# Sheet_esp32.net
KiCad netlist of a schematic drawn in Altium Designer
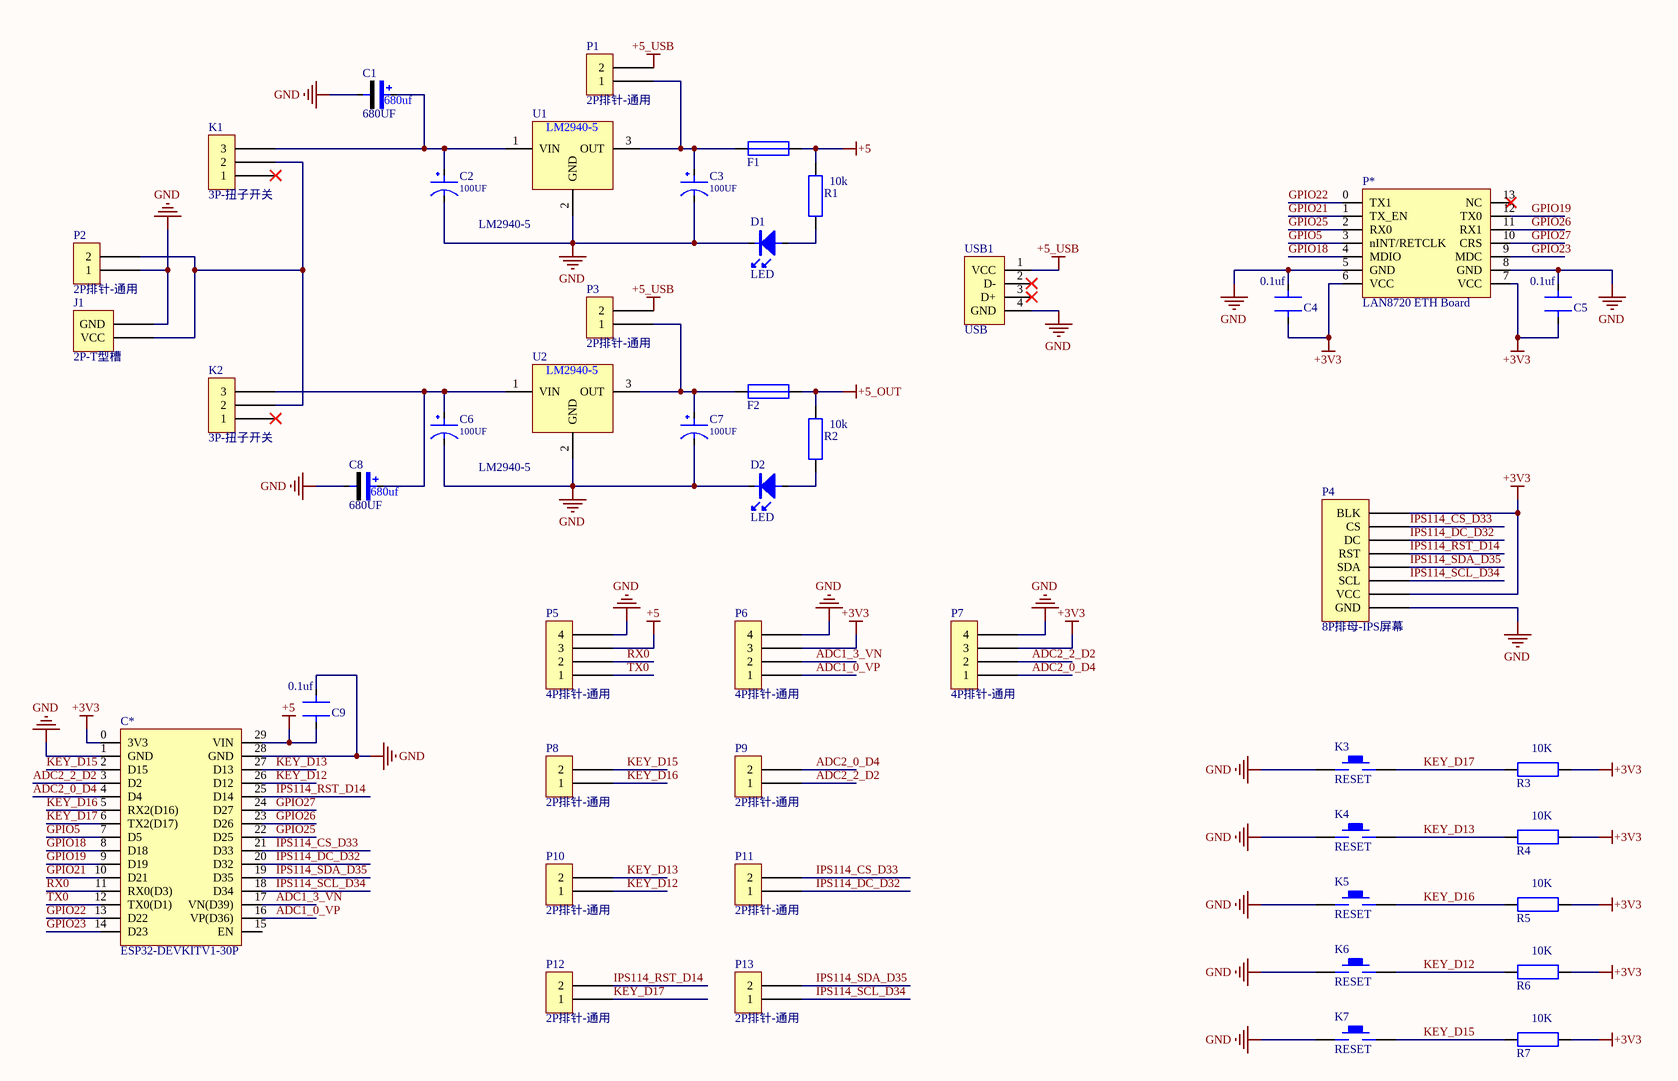
[diagram p0: Sheet_esp32.SchDoc]

(export (version "E")
  (design (tool "Eeschema 10.0.6"))
  (components
    (comp (ref "C*")
      (value "ESP32-DEVKITV1-30P")
      (footprint "ESP32-DEVKITV1-30P")
      (libsource (lib "Him_原理图库") (part "ESP32-DEVKITV1-30P"))
    )
    (comp (ref "C1")
      (value "680UF")
      (footprint "电容-直插680UF")
      (description "电源直插Capacitor")
      (libsource (lib "Him_原理图库") (part "电容-680UF"))
    )
    (comp (ref "C2")
      (value "100UF")
      (footprint "电容-直插680UF")
      (description "Capacitor")
      (libsource (lib "Him_原理图库") (part "电容2-通用"))
    )
    (comp (ref "C3")
      (value "100UF")
      (footprint "电容-直插680UF")
      (description "Capacitor")
      (libsource (lib "Him_原理图库") (part "电容2-通用"))
    )
    (comp (ref "C4")
      (value "0.1uf")
      (footprint "贴片0603-手工")
      (description "Capacitor")
      (fields (field (name "PUBLISHER") "Altium Limited"))
      (libsource (lib "Him_原理图库") (part "电容1-通用"))
    )
    (comp (ref "C5")
      (value "0.1uf")
      (footprint "贴片0603-手工")
      (description "Capacitor")
      (fields (field (name "PUBLISHER") "Altium Limited"))
      (libsource (lib "Him_原理图库") (part "电容1-通用"))
    )
    (comp (ref "C6")
      (value "100UF")
      (footprint "电容-直插680UF")
      (description "Capacitor")
      (libsource (lib "Him_原理图库") (part "电容2-通用"))
    )
    (comp (ref "C7")
      (value "100UF")
      (footprint "电容-直插680UF")
      (description "Capacitor")
      (libsource (lib "Him_原理图库") (part "电容2-通用"))
    )
    (comp (ref "C8")
      (value "680UF")
      (footprint "电容-直插680UF")
      (description "电源直插Capacitor")
      (libsource (lib "Him_原理图库") (part "电容-680UF"))
    )
    (comp (ref "C9")
      (value "0.1uf")
      (footprint "贴片0603-手工")
      (description "Capacitor")
      (fields (field (name "PUBLISHER") "Altium Limited"))
      (libsource (lib "Him_原理图库") (part "电容1-通用"))
    )
    (comp (ref "D1") (value "LED") (footprint "贴片0805-手工") (libsource (lib "Him_原理图库") (part "电灯-通用")))
    (comp (ref "D2") (value "LED") (footprint "贴片0805-手工") (libsource (lib "Him_原理图库") (part "电灯-通用")))
    (comp (ref "F1")
      (value "保险丝-通用")
      (footprint "贴片0805-手工")
      (fields (field (name "PUBLISHER") "Altium Limited"))
      (libsource (lib "Him_原理图库") (part "保险丝-通用"))
    )
    (comp (ref "F2")
      (value "保险丝-通用")
      (footprint "贴片0805-手工")
      (fields (field (name "PUBLISHER") "Altium Limited"))
      (libsource (lib "Him_原理图库") (part "保险丝-通用"))
    )
    (comp (ref "J1")
      (value "2P-T型槽")
      (footprint "T型槽-通用")
      (description "含引脚标记-电源")
      (fields (field (name "PUBLISHER") "Altium Limited"))
      (libsource (lib "Him_原理图库") (part "2P-T型槽"))
    )
    (comp (ref "K1")
      (value "3P-扭子开关")
      (footprint "扭子开关-直插通用")
      (description "中间那个是公共脚")
      (libsource (lib "Him_原理图库") (part "3P-扭子开关"))
    )
    (comp (ref "K2")
      (value "3P-扭子开关")
      (footprint "扭子开关-直插通用")
      (description "中间那个是公共脚")
      (libsource (lib "Him_原理图库") (part "3P-扭子开关"))
    )
    (comp (ref "K3")
      (value "RESET")
      (footprint "贴片按键-复位")
      (description "按键(弹性)-复位")
      (libsource (lib "Him_原理图库") (part "KEY-弹性复位"))
    )
    (comp (ref "K4")
      (value "RESET")
      (footprint "贴片按键-复位")
      (description "按键(弹性)-复位")
      (libsource (lib "Him_原理图库") (part "KEY-弹性复位"))
    )
    (comp (ref "K5")
      (value "RESET")
      (footprint "贴片按键-复位")
      (description "按键(弹性)-复位")
      (libsource (lib "Him_原理图库") (part "KEY-弹性复位"))
    )
    (comp (ref "K6")
      (value "RESET")
      (footprint "贴片按键-复位")
      (description "按键(弹性)-复位")
      (libsource (lib "Him_原理图库") (part "KEY-弹性复位"))
    )
    (comp (ref "K7")
      (value "RESET")
      (footprint "贴片按键-复位")
      (description "按键(弹性)-复位")
      (libsource (lib "Him_原理图库") (part "KEY-弹性复位"))
    )
    (comp (ref "P*")
      (value "LAN8720 ETH Board")
      (footprint "LAN8720 ETH Board")
      (description "LAN8720 网络模块 以太网收发器ETH RMII接口")
      (libsource (lib "Him_原理图库") (part "LAN8720 ETH Board"))
    )
    (comp (ref "P1")
      (value "2P排针-通用")
      (footprint "2p排针-通用")
      (fields (field (name "PUBLISHER") "Altium Limited"))
      (libsource (lib "Him_原理图库") (part "2P排针-通用"))
    )
    (comp (ref "P2")
      (value "2P排针-通用")
      (footprint "2P-KF2EDGK插头")
      (fields (field (name "PUBLISHER") "Altium Limited"))
      (libsource (lib "Him_原理图库") (part "2P排针-通用"))
    )
    (comp (ref "P3")
      (value "2P排针-通用")
      (footprint "2p排针-通用")
      (fields (field (name "PUBLISHER") "Altium Limited"))
      (libsource (lib "Him_原理图库") (part "2P排针-通用"))
    )
    (comp (ref "P4")
      (value "8P排母-IPS屏幕")
      (footprint "8P排母-IPS屏幕")
      (description "含引脚标记")
      (libsource (lib "Him_原理图库") (part "8P排母-IPS屏幕"))
    )
    (comp (ref "P5") (value "4P排针-通用") (footprint "4p排针-直插通用") (libsource (lib "Him_原理图库") (part "4P排针-通用")))
    (comp (ref "P6") (value "4P排针-通用") (footprint "4p排针-直插通用") (libsource (lib "Him_原理图库") (part "4P排针-通用")))
    (comp (ref "P7") (value "4P排针-通用") (footprint "4p排针-直插通用") (libsource (lib "Him_原理图库") (part "4P排针-通用")))
    (comp (ref "P8")
      (value "2P排针-通用")
      (footprint "2p排针-通用")
      (fields (field (name "PUBLISHER") "Altium Limited"))
      (libsource (lib "Him_原理图库") (part "2P排针-通用"))
    )
    (comp (ref "P9")
      (value "2P排针-通用")
      (footprint "2p排针-通用")
      (fields (field (name "PUBLISHER") "Altium Limited"))
      (libsource (lib "Him_原理图库") (part "2P排针-通用"))
    )
    (comp (ref "P10")
      (value "2P排针-通用")
      (footprint "2p排针-通用")
      (fields (field (name "PUBLISHER") "Altium Limited"))
      (libsource (lib "Him_原理图库") (part "2P排针-通用"))
    )
    (comp (ref "P11")
      (value "2P排针-通用")
      (footprint "2p排针-通用")
      (fields (field (name "PUBLISHER") "Altium Limited"))
      (libsource (lib "Him_原理图库") (part "2P排针-通用"))
    )
    (comp (ref "P12")
      (value "2P排针-通用")
      (footprint "2p排针-通用")
      (fields (field (name "PUBLISHER") "Altium Limited"))
      (libsource (lib "Him_原理图库") (part "2P排针-通用"))
    )
    (comp (ref "P13")
      (value "2P排针-通用")
      (footprint "2p排针-通用")
      (fields (field (name "PUBLISHER") "Altium Limited"))
      (libsource (lib "Him_原理图库") (part "2P排针-通用"))
    )
    (comp (ref "R1")
      (value "10k")
      (footprint "贴片0805-手工")
      (description "Resistor")
      (fields (field (name "PUBLISHER") "Altium Limited"))
      (libsource (lib "Him_原理图库") (part "电阻 - 通用"))
    )
    (comp (ref "R2")
      (value "10k")
      (footprint "贴片0805-手工")
      (description "Resistor")
      (fields (field (name "PUBLISHER") "Altium Limited"))
      (libsource (lib "Him_原理图库") (part "电阻 - 通用"))
    )
    (comp (ref "R3")
      (value "10K")
      (footprint "贴片0805-手工")
      (description "Resistor")
      (fields (field (name "PUBLISHER") "Altium Limited"))
      (libsource (lib "Him_原理图库") (part "电阻 - 通用"))
    )
    (comp (ref "R4")
      (value "10K")
      (footprint "贴片0805-手工")
      (description "Resistor")
      (fields (field (name "PUBLISHER") "Altium Limited"))
      (libsource (lib "Him_原理图库") (part "电阻 - 通用"))
    )
    (comp (ref "R5")
      (value "10K")
      (footprint "贴片0805-手工")
      (description "Resistor")
      (fields (field (name "PUBLISHER") "Altium Limited"))
      (libsource (lib "Him_原理图库") (part "电阻 - 通用"))
    )
    (comp (ref "R6")
      (value "10K")
      (footprint "贴片0805-手工")
      (description "Resistor")
      (fields (field (name "PUBLISHER") "Altium Limited"))
      (libsource (lib "Him_原理图库") (part "电阻 - 通用"))
    )
    (comp (ref "R7")
      (value "10K")
      (footprint "贴片0805-手工")
      (description "Resistor")
      (fields (field (name "PUBLISHER") "Altium Limited"))
      (libsource (lib "Him_原理图库") (part "电阻 - 通用"))
    )
    (comp (ref "U1")
      (value "LM2940-5")
      (footprint "3p排针-直插通用")
      (description "LM2940-5.0 五伏稳压 - 和LM1117不一样，中间脚是公共地")
      (libsource (lib "Him_原理图库") (part "LM2940-5"))
    )
    (comp (ref "U2")
      (value "LM2940-5")
      (footprint "3p排针-直插通用")
      (description "LM2940-5.0 五伏稳压 - 和LM1117不一样，中间脚是公共地")
      (libsource (lib "Him_原理图库") (part "LM2940-5"))
    )
    (comp (ref "USB1") (value "USB") (footprint "USB-A-F/P_B") (libsource (lib "Him_原理图库") (part "USB_G")))
  )
  (nets
    (net (code "1") (name "+3V3") (class "Default")
      (node (ref "C*") (pin "0") (pinfunction "3V3_0") (pintype "passive"))
      (node (ref "C4") (pin "1") (pinfunction "1_1") (pintype "passive"))
      (node (ref "C5") (pin "1") (pinfunction "1_1") (pintype "passive"))
      (node (ref "P*") (pin "6") (pinfunction "VCC_6") (pintype "passive"))
      (node (ref "P*") (pin "7") (pinfunction "VCC_7") (pintype "passive"))
      (node (ref "P4") (pin "2") (pinfunction "VCC_2") (pintype "passive"))
      (node (ref "P4") (pin "8") (pinfunction "BLK_8") (pintype "passive"))
      (node (ref "P6") (pin "3") (pinfunction "3_3") (pintype "passive"))
      (node (ref "P7") (pin "3") (pinfunction "3_3") (pintype "passive"))
      (node (ref "R3") (pin "1") (pinfunction "1_1") (pintype "passive"))
      (node (ref "R4") (pin "1") (pinfunction "1_1") (pintype "passive"))
      (node (ref "R5") (pin "1") (pinfunction "1_1") (pintype "passive"))
      (node (ref "R6") (pin "1") (pinfunction "1_1") (pintype "passive"))
      (node (ref "R7") (pin "1") (pinfunction "1_1") (pintype "passive"))
    )
    (net (code "2") (name "+5") (class "Default")
      (node (ref "C*") (pin "29") (pinfunction "VIN_29") (pintype "passive"))
      (node (ref "C9") (pin "1") (pinfunction "1_1") (pintype "passive"))
      (node (ref "F1") (pin "2") (pinfunction "2_2") (pintype "passive"))
      (node (ref "P5") (pin "3") (pinfunction "3_3") (pintype "passive"))
      (node (ref "R1") (pin "2") (pinfunction "2_2") (pintype "passive"))
    )
    (net (code "3") (name "+5_OUT") (class "Default")
      (node (ref "F2") (pin "2") (pinfunction "2_2") (pintype "passive"))
      (node (ref "R2") (pin "2") (pinfunction "2_2") (pintype "passive"))
    )
    (net (code "4") (name "+5_USB") (class "Default")
      (node (ref "P1") (pin "2") (pinfunction "2_2") (pintype "passive"))
      (node (ref "P3") (pin "2") (pinfunction "2_2") (pintype "passive"))
      (node (ref "USB1") (pin "1") (pinfunction "VCC_1") (pintype "passive"))
    )
    (net (code "5") (name "/ADC1_0_VP") (class "Default")
      (node (ref "C*") (pin "16") (pinfunction "VP(D36)_16") (pintype "passive"))
      (node (ref "P6") (pin "1") (pinfunction "1_1") (pintype "passive"))
    )
    (net (code "6") (name "/ADC1_3_VN") (class "Default")
      (node (ref "C*") (pin "17") (pinfunction "VN(D39)_17") (pintype "passive"))
      (node (ref "P6") (pin "2") (pinfunction "2_2") (pintype "passive"))
    )
    (net (code "7") (name "/ADC2_0_D4") (class "Default")
      (node (ref "C*") (pin "4") (pinfunction "D4_4") (pintype "passive"))
      (node (ref "P7") (pin "1") (pinfunction "1_1") (pintype "passive"))
      (node (ref "P9") (pin "2") (pinfunction "2_2") (pintype "passive"))
    )
    (net (code "8") (name "/ADC2_2_D2") (class "Default")
      (node (ref "C*") (pin "3") (pinfunction "D2_3") (pintype "passive"))
      (node (ref "P7") (pin "2") (pinfunction "2_2") (pintype "passive"))
      (node (ref "P9") (pin "1") (pinfunction "1_1") (pintype "passive"))
    )
    (net (code "9") (name "/GPIO5") (class "Default")
      (node (ref "C*") (pin "7") (pinfunction "D5_7") (pintype "passive"))
      (node (ref "P*") (pin "3") (pinfunction "nINT/RETCLK_3") (pintype "passive"))
    )
    (net (code "10") (name "/GPIO18") (class "Default")
      (node (ref "C*") (pin "8") (pinfunction "D18_8") (pintype "passive"))
      (node (ref "P*") (pin "4") (pinfunction "MDIO_4") (pintype "passive"))
    )
    (net (code "11") (name "/GPIO19") (class "Default")
      (node (ref "C*") (pin "9") (pinfunction "D19_9") (pintype "passive"))
      (node (ref "P*") (pin "12") (pinfunction "TX0_12") (pintype "passive"))
    )
    (net (code "12") (name "/GPIO21") (class "Default")
      (node (ref "C*") (pin "10") (pinfunction "D21_10") (pintype "passive"))
      (node (ref "P*") (pin "1") (pinfunction "TX_EN_1") (pintype "passive"))
    )
    (net (code "13") (name "/GPIO22") (class "Default")
      (node (ref "C*") (pin "13") (pinfunction "D22_13") (pintype "passive"))
      (node (ref "P*") (pin "0") (pinfunction "TX1_0") (pintype "passive"))
    )
    (net (code "14") (name "/GPIO23") (class "Default")
      (node (ref "C*") (pin "14") (pinfunction "D23_14") (pintype "passive"))
      (node (ref "P*") (pin "9") (pinfunction "MDC_9") (pintype "passive"))
    )
    (net (code "15") (name "/GPIO25") (class "Default")
      (node (ref "C*") (pin "22") (pinfunction "D25_22") (pintype "passive"))
      (node (ref "P*") (pin "2") (pinfunction "RX0_2") (pintype "passive"))
    )
    (net (code "16") (name "/GPIO26") (class "Default")
      (node (ref "C*") (pin "23") (pinfunction "D26_23") (pintype "passive"))
      (node (ref "P*") (pin "11") (pinfunction "RX1_11") (pintype "passive"))
    )
    (net (code "17") (name "/GPIO27") (class "Default")
      (node (ref "C*") (pin "24") (pinfunction "D27_24") (pintype "passive"))
      (node (ref "P*") (pin "10") (pinfunction "CRS_10") (pintype "passive"))
    )
    (net (code "18") (name "/IPS114_CS_D33") (class "Default")
      (node (ref "C*") (pin "21") (pinfunction "D33_21") (pintype "passive"))
      (node (ref "P11") (pin "2") (pinfunction "2_2") (pintype "passive"))
      (node (ref "P4") (pin "7") (pinfunction "CS_7") (pintype "passive"))
    )
    (net (code "19") (name "/IPS114_DC_D32") (class "Default")
      (node (ref "C*") (pin "20") (pinfunction "D32_20") (pintype "passive"))
      (node (ref "P11") (pin "1") (pinfunction "1_1") (pintype "passive"))
      (node (ref "P4") (pin "6") (pinfunction "DC_6") (pintype "passive"))
    )
    (net (code "20") (name "/IPS114_RST_D14") (class "Default")
      (node (ref "C*") (pin "25") (pinfunction "D14_25") (pintype "passive"))
      (node (ref "P12") (pin "2") (pinfunction "2_2") (pintype "passive"))
      (node (ref "P4") (pin "5") (pinfunction "RST_5") (pintype "passive"))
    )
    (net (code "21") (name "/IPS114_SCL_D34") (class "Default")
      (node (ref "C*") (pin "18") (pinfunction "D34_18") (pintype "passive"))
      (node (ref "P13") (pin "1") (pinfunction "1_1") (pintype "passive"))
      (node (ref "P4") (pin "3") (pinfunction "SCL_3") (pintype "passive"))
    )
    (net (code "22") (name "/IPS114_SDA_D35") (class "Default")
      (node (ref "C*") (pin "19") (pinfunction "D35_19") (pintype "passive"))
      (node (ref "P13") (pin "2") (pinfunction "2_2") (pintype "passive"))
      (node (ref "P4") (pin "4") (pinfunction "SDA_4") (pintype "passive"))
    )
    (net (code "23") (name "/KEY_D12") (class "Default")
      (node (ref "C*") (pin "26") (pinfunction "D12_26") (pintype "passive"))
      (node (ref "K6") (pin "2") (pinfunction "2_2") (pintype "passive"))
      (node (ref "P10") (pin "1") (pinfunction "1_1") (pintype "passive"))
      (node (ref "R6") (pin "2") (pinfunction "2_2") (pintype "passive"))
    )
    (net (code "24") (name "/KEY_D13") (class "Default")
      (node (ref "C*") (pin "27") (pinfunction "D13_27") (pintype "passive"))
      (node (ref "K4") (pin "2") (pinfunction "2_2") (pintype "passive"))
      (node (ref "P10") (pin "2") (pinfunction "2_2") (pintype "passive"))
      (node (ref "R4") (pin "2") (pinfunction "2_2") (pintype "passive"))
    )
    (net (code "25") (name "/KEY_D15") (class "Default")
      (node (ref "C*") (pin "2") (pinfunction "D15_2") (pintype "passive"))
      (node (ref "K7") (pin "2") (pinfunction "2_2") (pintype "passive"))
      (node (ref "P8") (pin "2") (pinfunction "2_2") (pintype "passive"))
      (node (ref "R7") (pin "2") (pinfunction "2_2") (pintype "passive"))
    )
    (net (code "26") (name "/KEY_D16") (class "Default")
      (node (ref "C*") (pin "5") (pinfunction "RX2(D16)_5") (pintype "passive"))
      (node (ref "K5") (pin "2") (pinfunction "2_2") (pintype "passive"))
      (node (ref "P8") (pin "1") (pinfunction "1_1") (pintype "passive"))
      (node (ref "R5") (pin "2") (pinfunction "2_2") (pintype "passive"))
    )
    (net (code "27") (name "/KEY_D17") (class "Default")
      (node (ref "C*") (pin "6") (pinfunction "TX2(D17)_6") (pintype "passive"))
      (node (ref "K3") (pin "2") (pinfunction "2_2") (pintype "passive"))
      (node (ref "P12") (pin "1") (pinfunction "1_1") (pintype "passive"))
      (node (ref "R3") (pin "2") (pinfunction "2_2") (pintype "passive"))
    )
    (net (code "28") (name "/RX0") (class "Default")
      (node (ref "C*") (pin "11") (pinfunction "RX0(D3)_11") (pintype "passive"))
      (node (ref "P5") (pin "2") (pinfunction "2_2") (pintype "passive"))
    )
    (net (code "29") (name "/TX0") (class "Default")
      (node (ref "C*") (pin "12") (pinfunction "TX0(D1)_12") (pintype "passive"))
      (node (ref "P5") (pin "1") (pinfunction "1_1") (pintype "passive"))
    )
    (net (code "30") (name "GND") (class "Default")
      (node (ref "C*") (pin "1") (pinfunction "GND_1") (pintype "passive"))
      (node (ref "C*") (pin "28") (pinfunction "GND_28") (pintype "passive"))
      (node (ref "C1") (pin "2") (pinfunction "2_2") (pintype "passive"))
      (node (ref "C2") (pin "2") (pinfunction "GND_2") (pintype "passive"))
      (node (ref "C3") (pin "2") (pinfunction "GND_2") (pintype "passive"))
      (node (ref "C4") (pin "2") (pinfunction "2_2") (pintype "passive"))
      (node (ref "C5") (pin "2") (pinfunction "2_2") (pintype "passive"))
      (node (ref "C6") (pin "2") (pinfunction "GND_2") (pintype "passive"))
      (node (ref "C7") (pin "2") (pinfunction "GND_2") (pintype "passive"))
      (node (ref "C8") (pin "2") (pinfunction "2_2") (pintype "passive"))
      (node (ref "C9") (pin "2") (pinfunction "2_2") (pintype "passive"))
      (node (ref "D1") (pin "2") (pinfunction "2_2") (pintype "passive"))
      (node (ref "D2") (pin "2") (pinfunction "2_2") (pintype "passive"))
      (node (ref "J1") (pin "2") (pinfunction "GND_2") (pintype "passive"))
      (node (ref "K3") (pin "1") (pinfunction "1_1") (pintype "passive"))
      (node (ref "K4") (pin "1") (pinfunction "1_1") (pintype "passive"))
      (node (ref "K5") (pin "1") (pinfunction "1_1") (pintype "passive"))
      (node (ref "K6") (pin "1") (pinfunction "1_1") (pintype "passive"))
      (node (ref "K7") (pin "1") (pinfunction "1_1") (pintype "passive"))
      (node (ref "P*") (pin "5") (pinfunction "GND_5") (pintype "passive"))
      (node (ref "P*") (pin "8") (pinfunction "GND_8") (pintype "passive"))
      (node (ref "P2") (pin "1") (pinfunction "1_1") (pintype "passive"))
      (node (ref "P4") (pin "1") (pinfunction "GND_1") (pintype "passive"))
      (node (ref "P5") (pin "4") (pinfunction "4_4") (pintype "passive"))
      (node (ref "P6") (pin "4") (pinfunction "4_4") (pintype "passive"))
      (node (ref "P7") (pin "4") (pinfunction "4_4") (pintype "passive"))
      (node (ref "U1") (pin "2") (pinfunction "GND_2") (pintype "passive"))
      (node (ref "U2") (pin "2") (pinfunction "GND_2") (pintype "passive"))
      (node (ref "USB1") (pin "4") (pinfunction "GND_4") (pintype "passive"))
    )
    (net (code "31") (name "Net-(C2-VCC)") (class "Default")
      (node (ref "C1") (pin "1") (pinfunction "1_1") (pintype "passive"))
      (node (ref "C2") (pin "1") (pinfunction "VCC_1") (pintype "passive"))
      (node (ref "K1") (pin "3") (pinfunction "3_3") (pintype "passive"))
      (node (ref "U1") (pin "1") (pinfunction "VIN_1") (pintype "passive"))
    )
    (net (code "32") (name "Net-(C3-VCC)") (class "Default")
      (node (ref "C3") (pin "1") (pinfunction "VCC_1") (pintype "passive"))
      (node (ref "F1") (pin "1") (pinfunction "1_1") (pintype "passive"))
      (node (ref "P1") (pin "1") (pinfunction "1_1") (pintype "passive"))
      (node (ref "U1") (pin "3") (pinfunction "OUT_3") (pintype "passive"))
    )
    (net (code "33") (name "Net-(C6-VCC)") (class "Default")
      (node (ref "C6") (pin "1") (pinfunction "VCC_1") (pintype "passive"))
      (node (ref "C8") (pin "1") (pinfunction "1_1") (pintype "passive"))
      (node (ref "K2") (pin "3") (pinfunction "3_3") (pintype "passive"))
      (node (ref "U2") (pin "1") (pinfunction "VIN_1") (pintype "passive"))
    )
    (net (code "34") (name "Net-(C7-VCC)") (class "Default")
      (node (ref "C7") (pin "1") (pinfunction "VCC_1") (pintype "passive"))
      (node (ref "F2") (pin "1") (pinfunction "1_1") (pintype "passive"))
      (node (ref "P3") (pin "1") (pinfunction "1_1") (pintype "passive"))
      (node (ref "U2") (pin "3") (pinfunction "OUT_3") (pintype "passive"))
    )
    (net (code "35") (name "Net-(D1-Pad1)") (class "Default")
      (node (ref "D1") (pin "1") (pinfunction "1_1") (pintype "passive"))
      (node (ref "R1") (pin "1") (pinfunction "1_1") (pintype "passive"))
    )
    (net (code "36") (name "Net-(D2-Pad1)") (class "Default")
      (node (ref "D2") (pin "1") (pinfunction "1_1") (pintype "passive"))
      (node (ref "R2") (pin "1") (pinfunction "1_1") (pintype "passive"))
    )
    (net (code "37") (name "Net-(J1-VCC)") (class "Default")
      (node (ref "J1") (pin "1") (pinfunction "VCC_1") (pintype "passive"))
      (node (ref "K1") (pin "2") (pinfunction "2_2") (pintype "passive"))
      (node (ref "K2") (pin "2") (pinfunction "2_2") (pintype "passive"))
      (node (ref "P2") (pin "2") (pinfunction "2_2") (pintype "passive"))
    )
    (net (code "38") (name "unconnected-(C*-EN-Pad15)") (class "Default")
      (node (ref "C*") (pin "15") (pinfunction "EN_15") (pintype "passive"))
    )
    (net (code "39") (name "unconnected-(K1-Pad1)") (class "Default")
      (node (ref "K1") (pin "1") (pinfunction "1_1") (pintype "passive+no_connect"))
    )
    (net (code "40") (name "unconnected-(K2-Pad1)") (class "Default")
      (node (ref "K2") (pin "1") (pinfunction "1_1") (pintype "passive+no_connect"))
    )
    (net (code "41") (name "unconnected-(P*-NC-Pad13)") (class "Default")
      (node (ref "P*") (pin "13") (pinfunction "NC_13") (pintype "passive+no_connect"))
    )
    (net (code "42") (name "unconnected-(USB1-D+-Pad3)") (class "Default")
      (node (ref "USB1") (pin "3") (pinfunction "D+_3") (pintype "passive+no_connect"))
    )
    (net (code "43") (name "unconnected-(USB1-D--Pad2)") (class "Default")
      (node (ref "USB1") (pin "2") (pinfunction "D-_2") (pintype "passive+no_connect"))
    )
  )
)
